# Control_Test_Board.net
KiCad netlist of a schematic drawn in Altium Designer
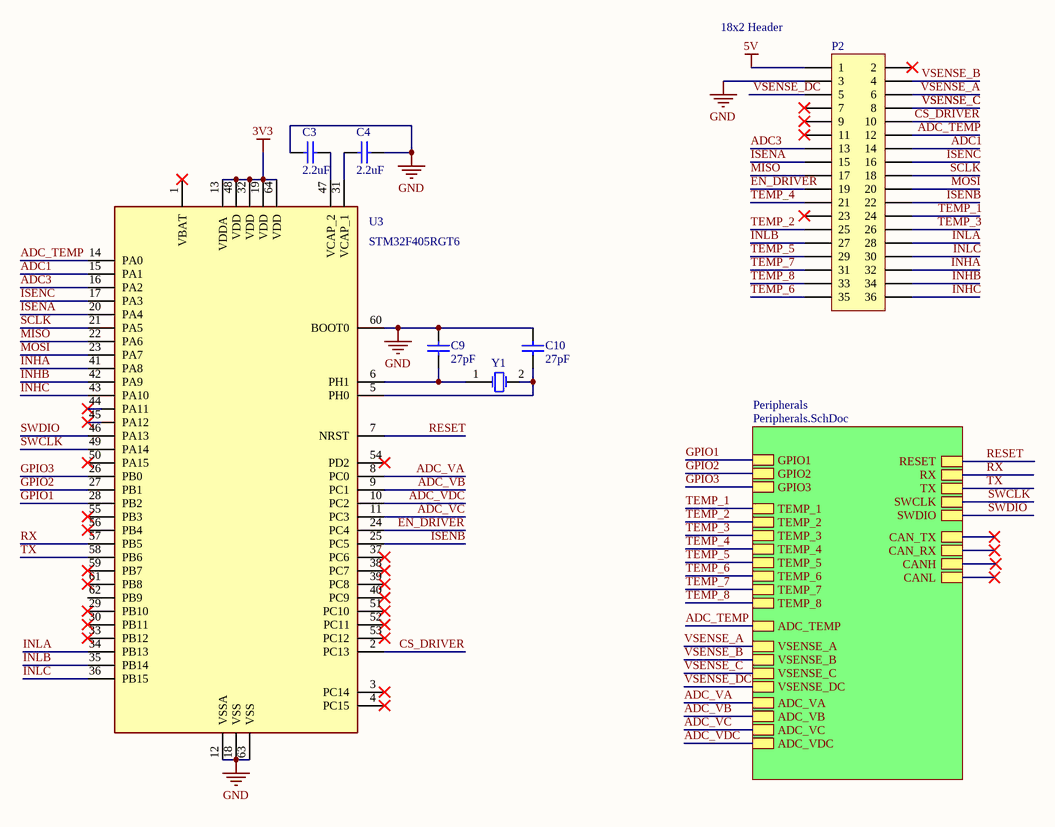
[diagram p0: Control_Test_Board.SchDoc]

(export (version "E")
  (design (tool "Eeschema 10.0.6"))
  (components
    (comp (ref "C3")
      (value "2.2uF")
      (footprint "0805 - Capacitor")
      (description "Nonpolarized Capacitor")
      (fields (field (name "Comment") "Capacitor - Nonpolarized"))
      (libsource (lib "General") (part "Capacitor - Nonpolarized"))
    )
    (comp (ref "C4")
      (value "2.2uF")
      (footprint "0805 - Capacitor")
      (description "Nonpolarized Capacitor")
      (fields (field (name "Comment") "Capacitor - Nonpolarized"))
      (libsource (lib "General") (part "Capacitor - Nonpolarized"))
    )
    (comp (ref "C9")
      (value "27pF")
      (footprint "0805 - Capacitor")
      (description "Nonpolarized Capacitor")
      (fields (field (name "Comment") "100V"))
      (libsource (lib "General") (part "Capacitor - Nonpolarized"))
    )
    (comp (ref "C10")
      (value "27pF")
      (footprint "0805 - Capacitor")
      (description "Nonpolarized Capacitor")
      (fields (field (name "Comment") "100V"))
      (libsource (lib "General") (part "Capacitor - Nonpolarized"))
    )
    (comp (ref "P2")
      (value "Header 18X2")
      (footprint "HDR2X18")
      (description "Header, 18-Pin, Dual row")
      (fields (field (name "PUBLISHER") "Altium Limited"))
      (libsource (lib "Miscellaneous Connectors") (part "Header 18X2"))
    )
    (comp (ref "U3")
      (value "STM32F405RGT6")
      (footprint "STM32F405RG")
      (description "ST 64-pin Micro")
      (fields (field (name "MANUFACTURER PART NUMBER") "STM32F405RG") (field (name "MANUFACTURER") "ST"))
      (libsource (lib "GeneralComponents") (part "STM32F405RGT6"))
    )
    (comp (ref "Y1")
      (value "Oscillator")
      (footprint "2-SMD NO LEAD CRSYSTAL")
      (description "Crystal Oscillator")
      (libsource (lib "General") (part "Oscillator"))
    )
  )
  (nets
    (net (code "1") (name "/ADC1") (class "Default")
      (node (ref "P2") (pin "14") (pinfunction "14_14") (pintype "passive"))
      (node (ref "U3") (pin "15") (pinfunction "PA1_15") (pintype "passive"))
    )
    (net (code "2") (name "/ADC3") (class "Default")
      (node (ref "P2") (pin "13") (pinfunction "13_13") (pintype "passive"))
      (node (ref "U3") (pin "16") (pinfunction "PA2_16") (pintype "passive"))
    )
    (net (code "3") (name "/ADC_TEMP") (class "Default")
      (node (ref "P2") (pin "12") (pinfunction "12_12") (pintype "passive"))
      (node (ref "U3") (pin "14") (pinfunction "PA0_14") (pintype "passive"))
    )
    (net (code "4") (name "/ADC_VA") (class "Default")
      (node (ref "U3") (pin "8") (pinfunction "PC0_8") (pintype "passive"))
    )
    (net (code "5") (name "/ADC_VB") (class "Default")
      (node (ref "U3") (pin "9") (pinfunction "PC1_9") (pintype "passive"))
    )
    (net (code "6") (name "/ADC_VC") (class "Default")
      (node (ref "U3") (pin "11") (pinfunction "PC3_11") (pintype "passive"))
    )
    (net (code "7") (name "/ADC_VDC") (class "Default")
      (node (ref "U3") (pin "10") (pinfunction "PC2_10") (pintype "passive"))
    )
    (net (code "12") (name "/CS_DRIVER") (class "Default")
      (node (ref "P2") (pin "10") (pinfunction "10_10") (pintype "passive"))
      (node (ref "U3") (pin "2") (pinfunction "PC13_2") (pintype "passive"))
    )
    (net (code "13") (name "/EN_DRIVER") (class "Default")
      (node (ref "P2") (pin "19") (pinfunction "19_19") (pintype "passive"))
      (node (ref "U3") (pin "24") (pinfunction "PC4_24") (pintype "passive"))
    )
    (net (code "14") (name "/GPIO1") (class "Default")
      (node (ref "U3") (pin "28") (pinfunction "PB2_28") (pintype "passive"))
    )
    (net (code "15") (name "/GPIO2") (class "Default")
      (node (ref "U3") (pin "27") (pinfunction "PB1_27") (pintype "passive"))
    )
    (net (code "16") (name "/GPIO3") (class "Default")
      (node (ref "U3") (pin "26") (pinfunction "PB0_26") (pintype "passive"))
    )
    (net (code "17") (name "/INHA") (class "Default")
      (node (ref "P2") (pin "32") (pinfunction "32_32") (pintype "passive"))
      (node (ref "U3") (pin "41") (pinfunction "PA8_41") (pintype "passive"))
    )
    (net (code "18") (name "/INHB") (class "Default")
      (node (ref "P2") (pin "34") (pinfunction "34_34") (pintype "passive"))
      (node (ref "U3") (pin "42") (pinfunction "PA9_42") (pintype "passive"))
    )
    (net (code "19") (name "/INHC") (class "Default")
      (node (ref "P2") (pin "36") (pinfunction "36_36") (pintype "passive"))
      (node (ref "U3") (pin "43") (pinfunction "PA10_43") (pintype "passive"))
    )
    (net (code "20") (name "/INLA") (class "Default")
      (node (ref "P2") (pin "28") (pinfunction "28_28") (pintype "passive"))
      (node (ref "U3") (pin "34") (pinfunction "PB13_34") (pintype "passive"))
    )
    (net (code "21") (name "/INLB") (class "Default")
      (node (ref "P2") (pin "27") (pinfunction "27_27") (pintype "passive"))
      (node (ref "U3") (pin "35") (pinfunction "PB14_35") (pintype "passive"))
    )
    (net (code "22") (name "/INLC") (class "Default")
      (node (ref "P2") (pin "30") (pinfunction "30_30") (pintype "passive"))
      (node (ref "U3") (pin "36") (pinfunction "PB15_36") (pintype "passive"))
    )
    (net (code "23") (name "/ISENA") (class "Default")
      (node (ref "P2") (pin "15") (pinfunction "15_15") (pintype "passive"))
      (node (ref "U3") (pin "20") (pinfunction "PA4_20") (pintype "passive"))
    )
    (net (code "24") (name "/ISENB") (class "Default")
      (node (ref "P2") (pin "22") (pinfunction "22_22") (pintype "passive"))
      (node (ref "U3") (pin "25") (pinfunction "PC5_25") (pintype "passive"))
    )
    (net (code "25") (name "/ISENC") (class "Default")
      (node (ref "P2") (pin "16") (pinfunction "16_16") (pintype "passive"))
      (node (ref "U3") (pin "17") (pinfunction "PA3_17") (pintype "passive"))
    )
    (net (code "26") (name "/MISO") (class "Default")
      (node (ref "P2") (pin "17") (pinfunction "17_17") (pintype "passive"))
      (node (ref "U3") (pin "22") (pinfunction "PA6_22") (pintype "passive"))
    )
    (net (code "27") (name "/MOSI") (class "Default")
      (node (ref "P2") (pin "20") (pinfunction "20_20") (pintype "passive"))
      (node (ref "U3") (pin "23") (pinfunction "PA7_23") (pintype "passive"))
    )
    (net (code "28") (name "/RESET") (class "Default")
      (node (ref "U3") (pin "7") (pinfunction "NRST_7") (pintype "passive"))
    )
    (net (code "29") (name "/RX") (class "Default")
      (node (ref "U3") (pin "57") (pinfunction "PB5_57") (pintype "passive"))
    )
    (net (code "30") (name "/SCLK") (class "Default")
      (node (ref "P2") (pin "18") (pinfunction "18_18") (pintype "passive"))
      (node (ref "U3") (pin "21") (pinfunction "PA5_21") (pintype "passive"))
    )
    (net (code "31") (name "/SWCLK") (class "Default")
      (node (ref "U3") (pin "49") (pinfunction "PA14_49") (pintype "passive"))
    )
    (net (code "32") (name "/SWDIO") (class "Default")
      (node (ref "U3") (pin "46") (pinfunction "PA13_46") (pintype "passive"))
    )
    (net (code "33") (name "/TEMP_1") (class "Default")
      (node (ref "P2") (pin "24") (pinfunction "24_24") (pintype "passive"))
    )
    (net (code "34") (name "/TEMP_2") (class "Default")
      (node (ref "P2") (pin "25") (pinfunction "25_25") (pintype "passive"))
    )
    (net (code "35") (name "/TEMP_3") (class "Default")
      (node (ref "P2") (pin "26") (pinfunction "26_26") (pintype "passive"))
    )
    (net (code "36") (name "/TEMP_4") (class "Default")
      (node (ref "P2") (pin "21") (pinfunction "21_21") (pintype "passive"))
    )
    (net (code "37") (name "/TEMP_5") (class "Default")
      (node (ref "P2") (pin "29") (pinfunction "29_29") (pintype "passive"))
    )
    (net (code "38") (name "/TEMP_6") (class "Default")
      (node (ref "P2") (pin "35") (pinfunction "35_35") (pintype "passive"))
    )
    (net (code "39") (name "/TEMP_7") (class "Default")
      (node (ref "P2") (pin "31") (pinfunction "31_31") (pintype "passive"))
    )
    (net (code "40") (name "/TEMP_8") (class "Default")
      (node (ref "P2") (pin "33") (pinfunction "33_33") (pintype "passive"))
    )
    (net (code "41") (name "/TX") (class "Default")
      (node (ref "U3") (pin "58") (pinfunction "PB6_58") (pintype "passive"))
    )
    (net (code "42") (name "/VSENSE_A") (class "Default")
      (node (ref "P2") (pin "6") (pinfunction "6_6") (pintype "passive"))
    )
    (net (code "43") (name "/VSENSE_B") (class "Default")
      (node (ref "P2") (pin "4") (pinfunction "4_4") (pintype "passive"))
    )
    (net (code "44") (name "/VSENSE_C") (class "Default")
      (node (ref "P2") (pin "8") (pinfunction "8_8") (pintype "passive"))
    )
    (net (code "45") (name "/VSENSE_DC") (class "Default")
      (node (ref "P2") (pin "5") (pinfunction "5_5") (pintype "passive"))
    )
    (net (code "46") (name "3V3") (class "Default")
      (node (ref "U3") (pin "13") (pinfunction "VDDA_13") (pintype "power_in"))
      (node (ref "U3") (pin "19") (pinfunction "VDD_19") (pintype "power_in"))
      (node (ref "U3") (pin "32") (pinfunction "VDD_32") (pintype "power_in"))
      (node (ref "U3") (pin "48") (pinfunction "VDD_48") (pintype "power_in"))
      (node (ref "U3") (pin "64") (pinfunction "VDD_64") (pintype "power_in"))
    )
    (net (code "47") (name "5V") (class "Default")
      (node (ref "P2") (pin "1") (pinfunction "1_1") (pintype "passive"))
    )
    (net (code "48") (name "GND") (class "Default")
      (node (ref "C10") (pin "2") (pinfunction "2_2") (pintype "passive"))
      (node (ref "C3") (pin "1") (pinfunction "1_1") (pintype "passive"))
      (node (ref "C4") (pin "2") (pinfunction "2_2") (pintype "passive"))
      (node (ref "C9") (pin "2") (pinfunction "2_2") (pintype "passive"))
      (node (ref "P2") (pin "3") (pinfunction "3_3") (pintype "passive"))
      (node (ref "U3") (pin "12") (pinfunction "VSSA_12") (pintype "power_in"))
      (node (ref "U3") (pin "18") (pinfunction "VSS_18") (pintype "power_in"))
      (node (ref "U3") (pin "60") (pinfunction "BOOT0_60") (pintype "passive"))
      (node (ref "U3") (pin "63") (pinfunction "VSS_63") (pintype "power_in"))
    )
    (net (code "49") (name "Net-(U3-PH0)") (class "Default")
      (node (ref "C10") (pin "1") (pinfunction "1_1") (pintype "passive"))
      (node (ref "U3") (pin "5") (pinfunction "PH0_5") (pintype "passive"))
      (node (ref "Y1") (pin "2") (pinfunction "OSC2_2") (pintype "passive"))
    )
    (net (code "50") (name "Net-(U3-PH1)") (class "Default")
      (node (ref "C9") (pin "1") (pinfunction "1_1") (pintype "passive"))
      (node (ref "U3") (pin "6") (pinfunction "PH1_6") (pintype "passive"))
      (node (ref "Y1") (pin "1") (pinfunction "OSC1_1") (pintype "passive"))
    )
    (net (code "51") (name "Net-(U3-VCAP_1)") (class "Default")
      (node (ref "C4") (pin "1") (pinfunction "1_1") (pintype "passive"))
      (node (ref "U3") (pin "31") (pinfunction "VCAP_1_31") (pintype "power_in"))
    )
    (net (code "52") (name "Net-(U3-VCAP_2)") (class "Default")
      (node (ref "C3") (pin "2") (pinfunction "2_2") (pintype "passive"))
      (node (ref "U3") (pin "47") (pinfunction "VCAP_2_47") (pintype "power_in"))
    )
    (net (code "53") (name "unconnected-(P2-Pad2)") (class "Default")
      (node (ref "P2") (pin "2") (pinfunction "2_2") (pintype "passive+no_connect"))
    )
    (net (code "54") (name "unconnected-(P2-Pad7)") (class "Default")
      (node (ref "P2") (pin "7") (pinfunction "7_7") (pintype "passive+no_connect"))
    )
    (net (code "55") (name "unconnected-(P2-Pad9)") (class "Default")
      (node (ref "P2") (pin "9") (pinfunction "9_9") (pintype "passive+no_connect"))
    )
    (net (code "56") (name "unconnected-(P2-Pad11)") (class "Default")
      (node (ref "P2") (pin "11") (pinfunction "11_11") (pintype "passive+no_connect"))
    )
    (net (code "57") (name "unconnected-(P2-Pad23)") (class "Default")
      (node (ref "P2") (pin "23") (pinfunction "23_23") (pintype "passive+no_connect"))
    )
    (net (code "58") (name "unconnected-(U3-PA11-Pad44)") (class "Default")
      (node (ref "U3") (pin "44") (pinfunction "PA11_44") (pintype "passive+no_connect"))
    )
    (net (code "59") (name "unconnected-(U3-PA12-Pad45)") (class "Default")
      (node (ref "U3") (pin "45") (pinfunction "PA12_45") (pintype "passive+no_connect"))
    )
    (net (code "60") (name "unconnected-(U3-PA15-Pad50)") (class "Default")
      (node (ref "U3") (pin "50") (pinfunction "PA15_50") (pintype "passive+no_connect"))
    )
    (net (code "61") (name "unconnected-(U3-PB3-Pad55)") (class "Default")
      (node (ref "U3") (pin "55") (pinfunction "PB3_55") (pintype "passive+no_connect"))
    )
    (net (code "62") (name "unconnected-(U3-PB4-Pad56)") (class "Default")
      (node (ref "U3") (pin "56") (pinfunction "PB4_56") (pintype "passive+no_connect"))
    )
    (net (code "63") (name "unconnected-(U3-PB7-Pad59)") (class "Default")
      (node (ref "U3") (pin "59") (pinfunction "PB7_59") (pintype "passive+no_connect"))
    )
    (net (code "64") (name "unconnected-(U3-PB8-Pad61)") (class "Default")
      (node (ref "U3") (pin "61") (pinfunction "PB8_61") (pintype "passive+no_connect"))
    )
    (net (code "65") (name "unconnected-(U3-PB9-Pad62)") (class "Default")
      (node (ref "U3") (pin "62") (pinfunction "PB9_62") (pintype "passive"))
    )
    (net (code "66") (name "unconnected-(U3-PB10-Pad29)") (class "Default")
      (node (ref "U3") (pin "29") (pinfunction "PB10_29") (pintype "passive+no_connect"))
    )
    (net (code "67") (name "unconnected-(U3-PB11-Pad30)") (class "Default")
      (node (ref "U3") (pin "30") (pinfunction "PB11_30") (pintype "passive+no_connect"))
    )
    (net (code "68") (name "unconnected-(U3-PB12-Pad33)") (class "Default")
      (node (ref "U3") (pin "33") (pinfunction "PB12_33") (pintype "passive+no_connect"))
    )
    (net (code "69") (name "unconnected-(U3-PC6-Pad37)") (class "Default")
      (node (ref "U3") (pin "37") (pinfunction "PC6_37") (pintype "passive+no_connect"))
    )
    (net (code "70") (name "unconnected-(U3-PC7-Pad38)") (class "Default")
      (node (ref "U3") (pin "38") (pinfunction "PC7_38") (pintype "passive+no_connect"))
    )
    (net (code "71") (name "unconnected-(U3-PC8-Pad39)") (class "Default")
      (node (ref "U3") (pin "39") (pinfunction "PC8_39") (pintype "passive+no_connect"))
    )
    (net (code "72") (name "unconnected-(U3-PC9-Pad40)") (class "Default")
      (node (ref "U3") (pin "40") (pinfunction "PC9_40") (pintype "passive+no_connect"))
    )
    (net (code "73") (name "unconnected-(U3-PC10-Pad51)") (class "Default")
      (node (ref "U3") (pin "51") (pinfunction "PC10_51") (pintype "passive+no_connect"))
    )
    (net (code "74") (name "unconnected-(U3-PC11-Pad52)") (class "Default")
      (node (ref "U3") (pin "52") (pinfunction "PC11_52") (pintype "passive+no_connect"))
    )
    (net (code "75") (name "unconnected-(U3-PC12-Pad53)") (class "Default")
      (node (ref "U3") (pin "53") (pinfunction "PC12_53") (pintype "passive+no_connect"))
    )
    (net (code "76") (name "unconnected-(U3-PC14-Pad3)") (class "Default")
      (node (ref "U3") (pin "3") (pinfunction "PC14_3") (pintype "passive+no_connect"))
    )
    (net (code "77") (name "unconnected-(U3-PC15-Pad4)") (class "Default")
      (node (ref "U3") (pin "4") (pinfunction "PC15_4") (pintype "passive+no_connect"))
    )
    (net (code "78") (name "unconnected-(U3-PD2-Pad54)") (class "Default")
      (node (ref "U3") (pin "54") (pinfunction "PD2_54") (pintype "passive+no_connect"))
    )
    (net (code "79") (name "unconnected-(U3-VBAT-Pad1)") (class "Default")
      (node (ref "U3") (pin "1") (pinfunction "VBAT_1") (pintype "power_in+no_connect"))
    )
  )
)
